# untitled.net
KiCad netlist of a schematic drawn in EAGLE
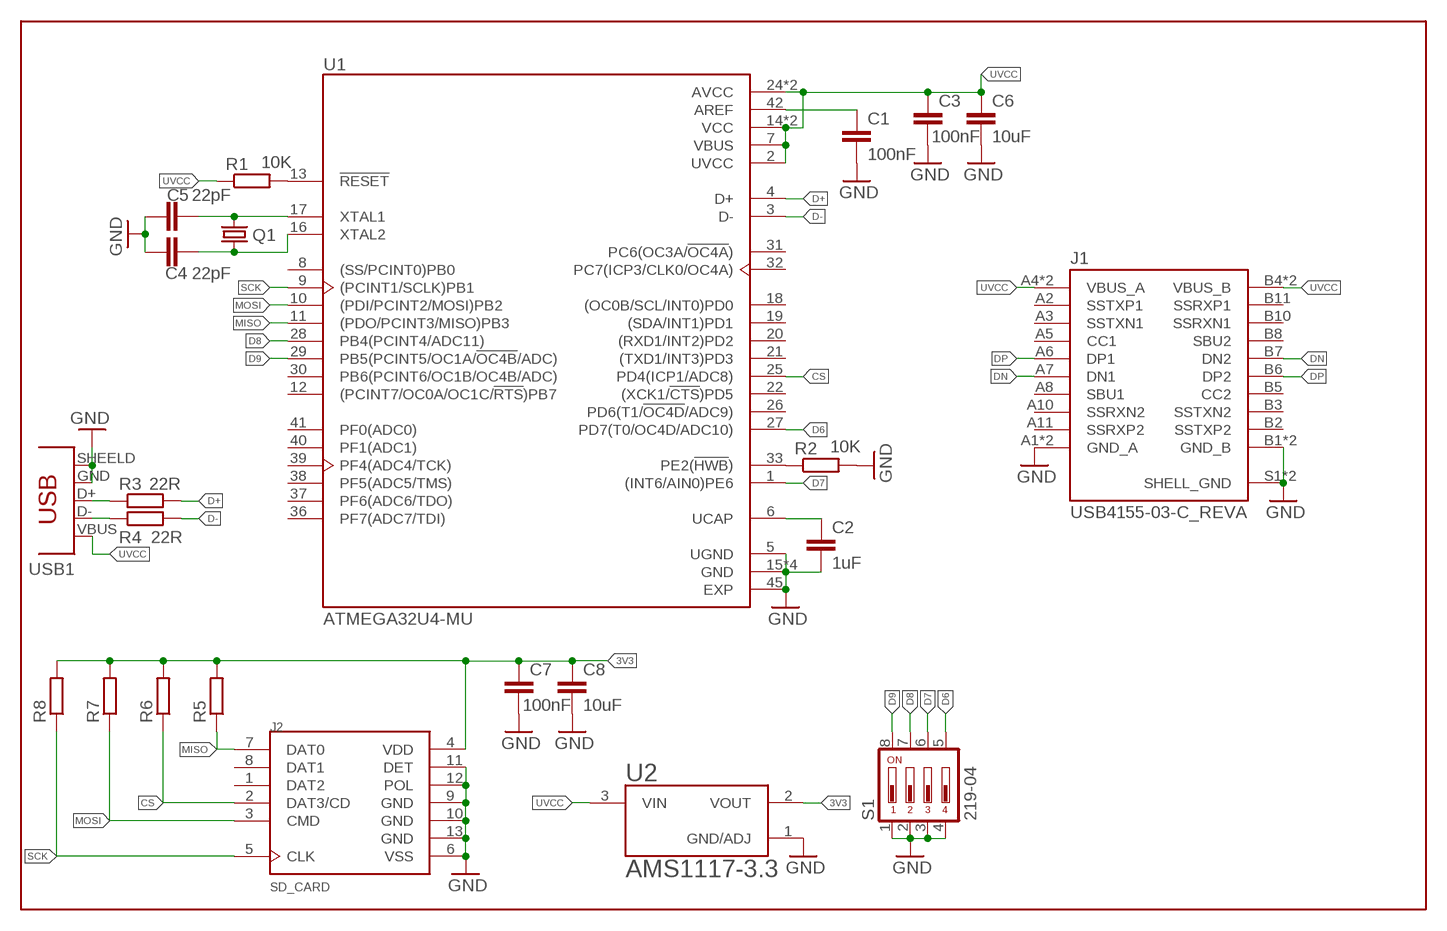
[diagram p0: schematic, sheet 1]

(export (version "E")
  (design (tool "Eeschema 10.0.6"))
  (components
    (comp (ref "C1")
      (value "100nF")
      (footprint "eagle-import:C0603")
      (libsource (lib "eagle-import") (part "C-EUC0603"))
    )
    (comp (ref "C2")
      (value "1uF")
      (footprint "eagle-import:C0603")
      (libsource (lib "eagle-import") (part "C-EUC0603"))
    )
    (comp (ref "C3")
      (value "100nF")
      (footprint "eagle-import:C0603")
      (libsource (lib "eagle-import") (part "C-EUC0603"))
    )
    (comp (ref "C4")
      (value "22pF")
      (footprint "eagle-import:C0603")
      (libsource (lib "eagle-import") (part "C-EUC0603"))
    )
    (comp (ref "C5")
      (value "22pF")
      (footprint "eagle-import:C0603")
      (libsource (lib "eagle-import") (part "C-EUC0603"))
    )
    (comp (ref "C6")
      (value "10uF")
      (footprint "eagle-import:C0603")
      (libsource (lib "eagle-import") (part "C-EUC0603"))
    )
    (comp (ref "C7")
      (value "100nF")
      (footprint "eagle-import:C0603")
      (libsource (lib "eagle-import") (part "C-EUC0603"))
    )
    (comp (ref "C8")
      (value "10uF")
      (footprint "eagle-import:C0603")
      (libsource (lib "eagle-import") (part "C-EUC0603"))
    )
    (comp (ref "J1")
      (value "USB4155-03-C_REVA")
      (footprint "eagle-import:GCT_USB4155-03-C_REVA")
      (fields (field (name "MF") "Global Connector Technology") (field (name "MP") "USB4155-03-C"))
      (libsource (lib "eagle-import") (part "USB4155-03-C_REVA"))
    )
    (comp (ref "J2")
      (value "SD_CARD")
      (footprint "eagle-import:MOLEX_0475710001")
      (fields (field (name "MF") "Molex") (field (name "MP") "47571-0001"))
      (libsource (lib "eagle-import") (part "0475710001"))
    )
    (comp (ref "Q1")
      (value "CRYSTALCTS406")
      (footprint "eagle-import:CTS406")
      (libsource (lib "eagle-import") (part "CRYSTALCTS406"))
    )
    (comp (ref "R1")
      (value "10K")
      (footprint "eagle-import:R0603")
      (libsource (lib "eagle-import") (part "R-EU_R0603"))
    )
    (comp (ref "R2")
      (value "10K")
      (footprint "eagle-import:R0603")
      (libsource (lib "eagle-import") (part "R-EU_R0603"))
    )
    (comp (ref "R3")
      (value "22R")
      (footprint "eagle-import:R0603")
      (libsource (lib "eagle-import") (part "R-EU_R0603"))
    )
    (comp (ref "R4")
      (value "22R")
      (footprint "eagle-import:R0603")
      (libsource (lib "eagle-import") (part "R-EU_R0603"))
    )
    (comp (ref "R5")
      (value "R-EU_R0603")
      (footprint "eagle-import:R0603")
      (libsource (lib "eagle-import") (part "R-EU_R0603"))
    )
    (comp (ref "R6")
      (value "R-EU_R0603")
      (footprint "eagle-import:R0603")
      (libsource (lib "eagle-import") (part "R-EU_R0603"))
    )
    (comp (ref "R7")
      (value "R-EU_R0603")
      (footprint "eagle-import:R0603")
      (libsource (lib "eagle-import") (part "R-EU_R0603"))
    )
    (comp (ref "R8")
      (value "R-EU_R0603")
      (footprint "eagle-import:R0603")
      (libsource (lib "eagle-import") (part "R-EU_R0603"))
    )
    (comp (ref "S1")
      (value "219-04")
      (footprint "eagle-import:CTS-219-04")
      (libsource (lib "eagle-import") (part "219-04"))
    )
    (comp (ref "U1")
      (value "ATMEGA32U4-MU")
      (footprint "eagle-import:QFN50P700X700X100-45N")
      (fields (field (name "MF") "Microchip"))
      (libsource (lib "eagle-import") (part "ATMEGA32U4-MU"))
    )
    (comp (ref "U2")
      (value "AMS1117-3.3")
      (footprint "eagle-import:SOT229P700X180-4N")
      (fields (field (name "MF") "Advanced Monolithic Systems"))
      (libsource (lib "eagle-import") (part "AMS1117-3.3"))
    )
    (comp (ref "USB1")
      (value "TYPE-A-MALE-SHILED")
      (footprint "eagle-import:TYPE-A-MALE")
      (libsource (lib "eagle-import") (part "TYPE-A-MALE-SHILED"))
    )
  )
  (nets
    (net (code "1") (name "3V3") (class "Default")
      (node (ref "C7") (pin "1") (pinfunction "1_1") (pintype "passive"))
      (node (ref "C8") (pin "1") (pinfunction "1_1") (pintype "passive"))
      (node (ref "J2") (pin "4") (pinfunction "VDD_4") (pintype "power_in"))
      (node (ref "R5") (pin "2") (pinfunction "2_2") (pintype "passive"))
      (node (ref "R6") (pin "2") (pinfunction "2_2") (pintype "passive"))
      (node (ref "R7") (pin "2") (pinfunction "2_2") (pintype "passive"))
      (node (ref "R8") (pin "2") (pinfunction "2_2") (pintype "passive"))
      (node (ref "U2") (pin "2") (pinfunction "VOUT_2") (pintype "output"))
    )
    (net (code "2") (name "CS") (class "Default")
      (node (ref "J2") (pin "2") (pinfunction "DAT3/CD_2") (pintype "bidirectional"))
      (node (ref "R6") (pin "1") (pinfunction "1_1") (pintype "passive"))
      (node (ref "U1") (pin "25") (pinfunction "PD4(ICP1/ADC8)_25") (pintype "bidirectional"))
    )
    (net (code "3") (name "D+") (class "Default")
      (node (ref "R3") (pin "2") (pinfunction "2_2") (pintype "passive"))
      (node (ref "U1") (pin "4") (pinfunction "D+_4") (pintype "bidirectional"))
    )
    (net (code "4") (name "D-") (class "Default")
      (node (ref "R4") (pin "2") (pinfunction "2_2") (pintype "passive"))
      (node (ref "U1") (pin "3") (pinfunction "D-_3") (pintype "bidirectional"))
    )
    (net (code "5") (name "D6") (class "Default")
      (node (ref "S1") (pin "5") (pinfunction "5_5") (pintype "passive"))
      (node (ref "U1") (pin "27") (pinfunction "PD7(T0/OC4D/ADC10)_27") (pintype "bidirectional"))
    )
    (net (code "6") (name "D7") (class "Default")
      (node (ref "S1") (pin "6") (pinfunction "6_6") (pintype "passive"))
      (node (ref "U1") (pin "1") (pinfunction "(INT6/AIN0)PE6_1") (pintype "bidirectional"))
    )
    (net (code "7") (name "D8") (class "Default")
      (node (ref "S1") (pin "7") (pinfunction "7_7") (pintype "passive"))
      (node (ref "U1") (pin "28") (pinfunction "PB4(PCINT4/ADC11)_28") (pintype "bidirectional"))
    )
    (net (code "8") (name "D9") (class "Default")
      (node (ref "S1") (pin "8") (pinfunction "8_8") (pintype "passive"))
      (node (ref "U1") (pin "29") (pinfunction "PB5(PCINT5/OC1A/~{OC4B}/ADC)_29") (pintype "bidirectional"))
    )
    (net (code "9") (name "DN") (class "Default")
      (node (ref "J1") (pin "A7") (pinfunction "DN1_A7") (pintype "bidirectional"))
      (node (ref "J1") (pin "B7") (pinfunction "DN2_B7") (pintype "bidirectional"))
      (node (ref "R4") (pin "1") (pinfunction "1_1") (pintype "passive"))
      (node (ref "USB1") (pin "D-") (pinfunction "2_D-") (pintype "passive"))
    )
    (net (code "10") (name "DP") (class "Default")
      (node (ref "J1") (pin "A6") (pinfunction "DP1_A6") (pintype "bidirectional"))
      (node (ref "J1") (pin "B6") (pinfunction "DP2_B6") (pintype "bidirectional"))
      (node (ref "R3") (pin "1") (pinfunction "1_1") (pintype "passive"))
      (node (ref "USB1") (pin "D+") (pinfunction "3_D+") (pintype "passive"))
    )
    (net (code "11") (name "GND") (class "Default")
      (node (ref "C1") (pin "2") (pinfunction "2_2") (pintype "passive"))
      (node (ref "C2") (pin "2") (pinfunction "2_2") (pintype "passive"))
      (node (ref "C3") (pin "2") (pinfunction "2_2") (pintype "passive"))
      (node (ref "C4") (pin "1") (pinfunction "1_1") (pintype "passive"))
      (node (ref "C5") (pin "1") (pinfunction "1_1") (pintype "passive"))
      (node (ref "C6") (pin "2") (pinfunction "2_2") (pintype "passive"))
      (node (ref "C7") (pin "2") (pinfunction "2_2") (pintype "passive"))
      (node (ref "C8") (pin "2") (pinfunction "2_2") (pintype "passive"))
      (node (ref "J1") (pin "A1") (pinfunction "GND_A_A1") (pintype "power_in"))
      (node (ref "J1") (pin "A12") (pinfunction "GND_A_A12") (pintype "power_in"))
      (node (ref "J1") (pin "B1") (pinfunction "GND_B_B1") (pintype "power_in"))
      (node (ref "J1") (pin "B12") (pinfunction "GND_B_B12") (pintype "power_in"))
      (node (ref "J1") (pin "S1") (pinfunction "SHELL_GND_S1") (pintype "power_in"))
      (node (ref "J1") (pin "S2") (pinfunction "SHELL_GND_S2") (pintype "power_in"))
      (node (ref "J2") (pin "10") (pinfunction "GND_10") (pintype "power_in"))
      (node (ref "J2") (pin "11") (pinfunction "DET_11") (pintype "passive"))
      (node (ref "J2") (pin "12") (pinfunction "POL_12") (pintype "passive"))
      (node (ref "J2") (pin "13") (pinfunction "GND_13") (pintype "power_in"))
      (node (ref "J2") (pin "6") (pinfunction "VSS_6") (pintype "power_in"))
      (node (ref "J2") (pin "9") (pinfunction "GND_9") (pintype "power_in"))
      (node (ref "R2") (pin "2") (pinfunction "2_2") (pintype "passive"))
      (node (ref "S1") (pin "1") (pinfunction "1_1") (pintype "passive"))
      (node (ref "S1") (pin "2") (pinfunction "2_2") (pintype "passive"))
      (node (ref "S1") (pin "3") (pinfunction "3_3") (pintype "passive"))
      (node (ref "S1") (pin "4") (pinfunction "4_4") (pintype "passive"))
      (node (ref "U1") (pin "15") (pinfunction "GND_15") (pintype "power_in"))
      (node (ref "U1") (pin "23") (pinfunction "GND_23") (pintype "power_in"))
      (node (ref "U1") (pin "35") (pinfunction "GND_35") (pintype "power_in"))
      (node (ref "U1") (pin "43") (pinfunction "GND_43") (pintype "power_in"))
      (node (ref "U1") (pin "45") (pinfunction "EXP_45") (pintype "passive"))
      (node (ref "U1") (pin "5") (pinfunction "UGND_5") (pintype "power_in"))
      (node (ref "U2") (pin "1") (pinfunction "GND/ADJ_1") (pintype "power_in"))
      (node (ref "USB1") (pin "GND") (pinfunction "4_GND") (pintype "power_in"))
      (node (ref "USB1") (pin "SHEELD") (pinfunction "5_SHEELD") (pintype "passive"))
    )
    (net (code "12") (name "MISO") (class "Default")
      (node (ref "J2") (pin "7") (pinfunction "DAT0_7") (pintype "bidirectional"))
      (node (ref "R5") (pin "1") (pinfunction "1_1") (pintype "passive"))
      (node (ref "U1") (pin "11") (pinfunction "(PDO/PCINT3/MISO)PB3_11") (pintype "bidirectional"))
    )
    (net (code "13") (name "MOSI") (class "Default")
      (node (ref "J2") (pin "3") (pinfunction "CMD_3") (pintype "bidirectional"))
      (node (ref "R7") (pin "1") (pinfunction "1_1") (pintype "passive"))
      (node (ref "U1") (pin "10") (pinfunction "(PDI/PCINT2/MOSI)PB2_10") (pintype "bidirectional"))
    )
    (net (code "14") (name "Net-(Q1-2)") (class "Default")
      (node (ref "C5") (pin "2") (pinfunction "2_2") (pintype "passive"))
      (node (ref "Q1") (pin "3") (pinfunction "2_3") (pintype "passive"))
      (node (ref "U1") (pin "17") (pinfunction "XTAL1_17") (pintype "input"))
    )
    (net (code "15") (name "Net-(U1-AREF)") (class "Default")
      (node (ref "C1") (pin "1") (pinfunction "1_1") (pintype "passive"))
      (node (ref "U1") (pin "42") (pinfunction "AREF_42") (pintype "power_in"))
    )
    (net (code "16") (name "Net-(U1-PE2(~{HWB}))") (class "Default")
      (node (ref "R2") (pin "1") (pinfunction "1_1") (pintype "passive"))
      (node (ref "U1") (pin "33") (pinfunction "PE2(~{HWB})_33") (pintype "bidirectional"))
    )
    (net (code "17") (name "Net-(U1-UCAP)") (class "Default")
      (node (ref "C2") (pin "1") (pinfunction "1_1") (pintype "passive"))
      (node (ref "U1") (pin "6") (pinfunction "UCAP_6") (pintype "passive"))
    )
    (net (code "18") (name "Net-(U1-XTAL2)") (class "Default")
      (node (ref "C4") (pin "2") (pinfunction "2_2") (pintype "passive"))
      (node (ref "Q1") (pin "1") (pinfunction "1_1") (pintype "passive"))
      (node (ref "U1") (pin "16") (pinfunction "XTAL2_16") (pintype "output"))
    )
    (net (code "19") (name "Net-(U1-~{RESET})") (class "Default")
      (node (ref "R1") (pin "2") (pinfunction "2_2") (pintype "passive"))
      (node (ref "U1") (pin "13") (pinfunction "~{RESET}_13") (pintype "input"))
    )
    (net (code "20") (name "SCK") (class "Default")
      (node (ref "J2") (pin "5") (pinfunction "CLK_5") (pintype "bidirectional"))
      (node (ref "R8") (pin "1") (pinfunction "1_1") (pintype "passive"))
      (node (ref "U1") (pin "9") (pinfunction "(PCINT1/SCLK)PB1_9") (pintype "bidirectional"))
    )
    (net (code "21") (name "UVCC") (class "Default")
      (node (ref "C3") (pin "1") (pinfunction "1_1") (pintype "passive"))
      (node (ref "C6") (pin "1") (pinfunction "1_1") (pintype "passive"))
      (node (ref "J1") (pin "A4") (pinfunction "VBUS_A_A4") (pintype "power_in"))
      (node (ref "J1") (pin "A9") (pinfunction "VBUS_A_A9") (pintype "power_in"))
      (node (ref "J1") (pin "B4") (pinfunction "VBUS_B_B4") (pintype "power_in"))
      (node (ref "J1") (pin "B9") (pinfunction "VBUS_B_B9") (pintype "power_in"))
      (node (ref "R1") (pin "1") (pinfunction "1_1") (pintype "passive"))
      (node (ref "U1") (pin "14") (pinfunction "VCC_14") (pintype "power_in"))
      (node (ref "U1") (pin "2") (pinfunction "UVCC_2") (pintype "power_in"))
      (node (ref "U1") (pin "24") (pinfunction "AVCC_24") (pintype "power_in"))
      (node (ref "U1") (pin "34") (pinfunction "VCC_34") (pintype "power_in"))
      (node (ref "U1") (pin "44") (pinfunction "AVCC_44") (pintype "power_in"))
      (node (ref "U1") (pin "7") (pinfunction "VBUS_7") (pintype "power_in"))
      (node (ref "U2") (pin "3") (pinfunction "VIN_3") (pintype "input"))
      (node (ref "USB1") (pin "VBUS") (pinfunction "1_VBUS") (pintype "power_in"))
    )
    (net (code "22") (name "unconnected-(J1-CC1-PadA5)") (class "Default")
      (node (ref "J1") (pin "A5") (pinfunction "CC1_A5") (pintype "bidirectional"))
    )
    (net (code "23") (name "unconnected-(J1-CC2-PadB5)") (class "Default")
      (node (ref "J1") (pin "B5") (pinfunction "CC2_B5") (pintype "bidirectional"))
    )
    (net (code "24") (name "unconnected-(J1-SBU1-PadA8)") (class "Default")
      (node (ref "J1") (pin "A8") (pinfunction "SBU1_A8") (pintype "bidirectional"))
    )
    (net (code "25") (name "unconnected-(J1-SBU2-PadB8)") (class "Default")
      (node (ref "J1") (pin "B8") (pinfunction "SBU2_B8") (pintype "bidirectional"))
    )
    (net (code "26") (name "unconnected-(J1-SSRXN1-PadB10)") (class "Default")
      (node (ref "J1") (pin "B10") (pinfunction "SSRXN1_B10") (pintype "bidirectional"))
    )
    (net (code "27") (name "unconnected-(J1-SSRXN2-PadA10)") (class "Default")
      (node (ref "J1") (pin "A10") (pinfunction "SSRXN2_A10") (pintype "bidirectional"))
    )
    (net (code "28") (name "unconnected-(J1-SSRXP1-PadB11)") (class "Default")
      (node (ref "J1") (pin "B11") (pinfunction "SSRXP1_B11") (pintype "bidirectional"))
    )
    (net (code "29") (name "unconnected-(J1-SSRXP2-PadA11)") (class "Default")
      (node (ref "J1") (pin "A11") (pinfunction "SSRXP2_A11") (pintype "bidirectional"))
    )
    (net (code "30") (name "unconnected-(J1-SSTXN1-PadA3)") (class "Default")
      (node (ref "J1") (pin "A3") (pinfunction "SSTXN1_A3") (pintype "bidirectional"))
    )
    (net (code "31") (name "unconnected-(J1-SSTXN2-PadB3)") (class "Default")
      (node (ref "J1") (pin "B3") (pinfunction "SSTXN2_B3") (pintype "bidirectional"))
    )
    (net (code "32") (name "unconnected-(J1-SSTXP1-PadA2)") (class "Default")
      (node (ref "J1") (pin "A2") (pinfunction "SSTXP1_A2") (pintype "bidirectional"))
    )
    (net (code "33") (name "unconnected-(J1-SSTXP2-PadB2)") (class "Default")
      (node (ref "J1") (pin "B2") (pinfunction "SSTXP2_B2") (pintype "bidirectional"))
    )
    (net (code "34") (name "unconnected-(J2-DAT1-Pad8)") (class "Default")
      (node (ref "J2") (pin "8") (pinfunction "DAT1_8") (pintype "bidirectional"))
    )
    (net (code "35") (name "unconnected-(J2-DAT2-Pad1)") (class "Default")
      (node (ref "J2") (pin "1") (pinfunction "DAT2_1") (pintype "bidirectional"))
    )
    (net (code "36") (name "unconnected-(U1-(OC0B{slash}SCL{slash}INT0)PD0-Pad18)") (class "Default")
      (node (ref "U1") (pin "18") (pinfunction "(OC0B/SCL/INT0)PD0_18") (pintype "bidirectional"))
    )
    (net (code "37") (name "unconnected-(U1-(PCINT7{slash}OC0A{slash}OC1C{slash}~{RTS})PB7-Pad12)") (class "Default")
      (node (ref "U1") (pin "12") (pinfunction "(PCINT7/OC0A/OC1C/~{RTS})PB7_12") (pintype "bidirectional"))
    )
    (net (code "38") (name "unconnected-(U1-(RXD1{slash}INT2)PD2-Pad20)") (class "Default")
      (node (ref "U1") (pin "20") (pinfunction "(RXD1/INT2)PD2_20") (pintype "bidirectional"))
    )
    (net (code "39") (name "unconnected-(U1-(SDA{slash}INT1)PD1-Pad19)") (class "Default")
      (node (ref "U1") (pin "19") (pinfunction "(SDA/INT1)PD1_19") (pintype "bidirectional"))
    )
    (net (code "40") (name "unconnected-(U1-(SS{slash}PCINT0)PB0-Pad8)") (class "Default")
      (node (ref "U1") (pin "8") (pinfunction "(SS/PCINT0)PB0_8") (pintype "bidirectional"))
    )
    (net (code "41") (name "unconnected-(U1-(TXD1{slash}INT3)PD3-Pad21)") (class "Default")
      (node (ref "U1") (pin "21") (pinfunction "(TXD1/INT3)PD3_21") (pintype "bidirectional"))
    )
    (net (code "42") (name "unconnected-(U1-(XCK1{slash}~{CTS})PD5-Pad22)") (class "Default")
      (node (ref "U1") (pin "22") (pinfunction "(XCK1/~{CTS})PD5_22") (pintype "bidirectional"))
    )
    (net (code "43") (name "unconnected-(U1-PB6(PCINT6{slash}OC1B{slash}OC4B{slash}ADC)-Pad30)") (class "Default")
      (node (ref "U1") (pin "30") (pinfunction "PB6(PCINT6/OC1B/OC4B/ADC)_30") (pintype "bidirectional"))
    )
    (net (code "44") (name "unconnected-(U1-PC6(OC3A{slash}~{OC4A})-Pad31)") (class "Default")
      (node (ref "U1") (pin "31") (pinfunction "PC6(OC3A/~{OC4A})_31") (pintype "bidirectional"))
    )
    (net (code "45") (name "unconnected-(U1-PC7(ICP3{slash}CLK0{slash}OC4A)-Pad32)") (class "Default")
      (node (ref "U1") (pin "32") (pinfunction "PC7(ICP3/CLK0/OC4A)_32") (pintype "bidirectional"))
    )
    (net (code "46") (name "unconnected-(U1-PD6(T1{slash}~{OC4D}{slash}ADC9)-Pad26)") (class "Default")
      (node (ref "U1") (pin "26") (pinfunction "PD6(T1/~{OC4D}/ADC9)_26") (pintype "bidirectional"))
    )
    (net (code "47") (name "unconnected-(U1-PF0(ADC0)-Pad41)") (class "Default")
      (node (ref "U1") (pin "41") (pinfunction "PF0(ADC0)_41") (pintype "bidirectional"))
    )
    (net (code "48") (name "unconnected-(U1-PF1(ADC1)-Pad40)") (class "Default")
      (node (ref "U1") (pin "40") (pinfunction "PF1(ADC1)_40") (pintype "bidirectional"))
    )
    (net (code "49") (name "unconnected-(U1-PF4(ADC4{slash}TCK)-Pad39)") (class "Default")
      (node (ref "U1") (pin "39") (pinfunction "PF4(ADC4/TCK)_39") (pintype "bidirectional"))
    )
    (net (code "50") (name "unconnected-(U1-PF5(ADC5{slash}TMS)-Pad38)") (class "Default")
      (node (ref "U1") (pin "38") (pinfunction "PF5(ADC5/TMS)_38") (pintype "bidirectional"))
    )
    (net (code "51") (name "unconnected-(U1-PF6(ADC6{slash}TDO)-Pad37)") (class "Default")
      (node (ref "U1") (pin "37") (pinfunction "PF6(ADC6/TDO)_37") (pintype "bidirectional"))
    )
    (net (code "52") (name "unconnected-(U1-PF7(ADC7{slash}TDI)-Pad36)") (class "Default")
      (node (ref "U1") (pin "36") (pinfunction "PF7(ADC7/TDI)_36") (pintype "bidirectional"))
    )
  )
)
